# Sch1r2.net
KiCad netlist of a schematic drawn in EAGLE
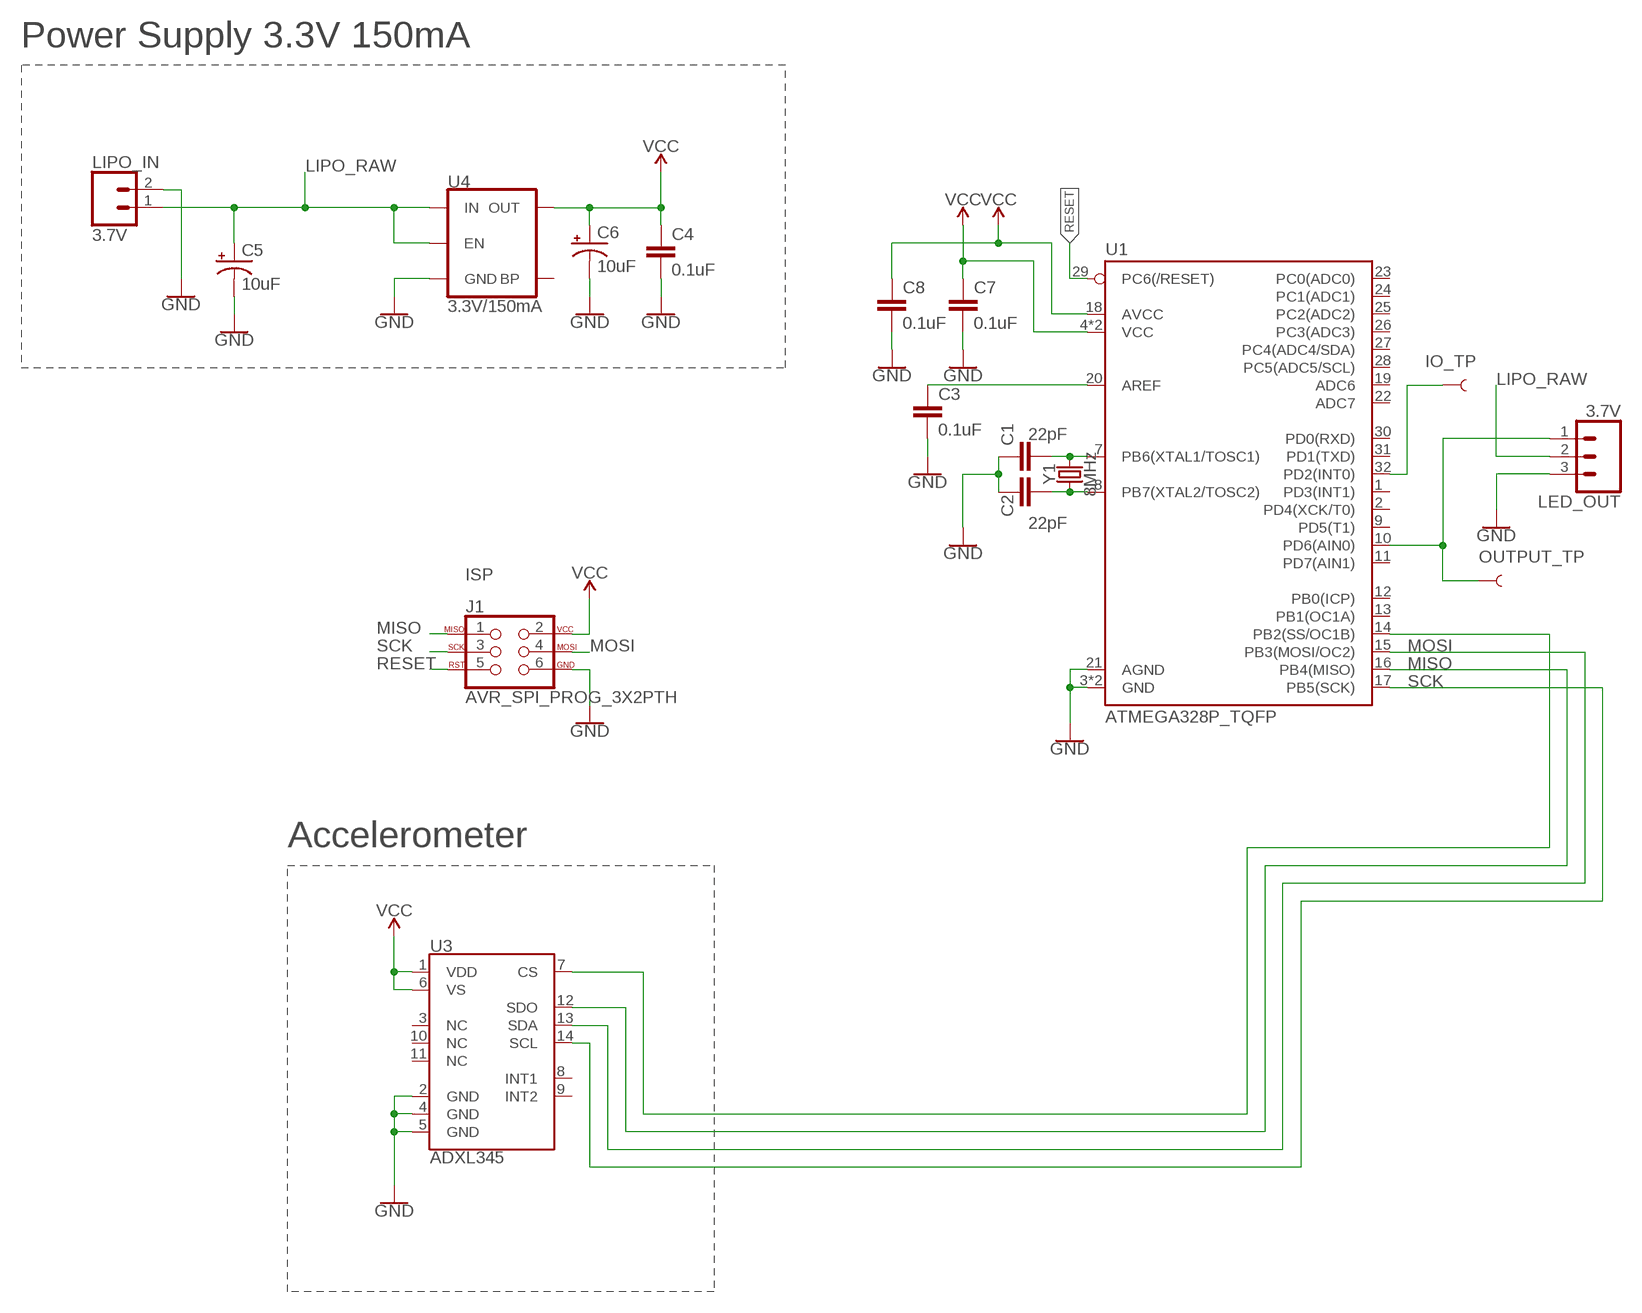
[diagram p0: schematic, sheet 1]

(export (version "E")
  (design (tool "Eeschema 10.0.6"))
  (components
    (comp (ref "C1")
      (value "22pF")
      (footprint "eagle-import:0603")
      (libsource (lib "eagle-import") (part "22PF-0603-50V-5%"))
    )
    (comp (ref "C2")
      (value "22pF")
      (footprint "eagle-import:0603")
      (libsource (lib "eagle-import") (part "22PF-0603-50V-5%"))
    )
    (comp (ref "C3")
      (value "0.1uF")
      (footprint "eagle-import:0402")
      (libsource (lib "eagle-import") (part "0.1UF-0402-16V-10%"))
    )
    (comp (ref "C4")
      (value "0.1uF")
      (footprint "eagle-import:0603")
      (libsource (lib "eagle-import") (part "0.1UF-0603-25V-(+80/-20%)"))
    )
    (comp (ref "C5")
      (value "10uF")
      (footprint "eagle-import:0603-POLAR")
      (libsource (lib "eagle-import") (part "10UF-POLAR-0603-6.3V-20%(TANT)"))
    )
    (comp (ref "C6")
      (value "10uF")
      (footprint "eagle-import:0603-POLAR")
      (libsource (lib "eagle-import") (part "10UF-POLAR-0603-6.3V-20%(TANT)"))
    )
    (comp (ref "C7")
      (value "0.1uF")
      (footprint "eagle-import:0402")
      (libsource (lib "eagle-import") (part "0.1UF-0402-16V-10%"))
    )
    (comp (ref "C8")
      (value "0.1uF")
      (footprint "eagle-import:0402")
      (libsource (lib "eagle-import") (part "0.1UF-0402-16V-10%"))
    )
    (comp (ref "IO_TP")
      (value "TEST-POINT3")
      (footprint "eagle-import:PAD.03X.03")
      (libsource (lib "eagle-import") (part "TEST-POINT3"))
    )
    (comp (ref "J1")
      (value "AVR_SPI_PROG_3X2PTH")
      (footprint "eagle-import:2X3")
      (libsource (lib "eagle-import") (part "AVR_SPI_PROG_3X2PTH"))
    )
    (comp (ref "LED_OUT")
      (value "3.7V")
      (footprint "eagle-import:1X03_LOCK_LONGPADS")
      (libsource (lib "eagle-import") (part "CONN_03LOCK_LONGPADS"))
    )
    (comp (ref "LIPO_IN")
      (value "3.7V")
      (footprint "eagle-import:1X02_LONGPADS")
      (libsource (lib "eagle-import") (part "CONN_02PTH3"))
    )
    (comp (ref "OUTPUT_TP")
      (value "TEST-POINT3")
      (footprint "eagle-import:PAD.03X.03")
      (libsource (lib "eagle-import") (part "TEST-POINT3"))
    )
    (comp (ref "U1")
      (value "ATMEGA328P_TQFP")
      (footprint "eagle-import:TQFP32-08")
      (libsource (lib "eagle-import") (part "ATMEGA328P_TQFP"))
    )
    (comp (ref "U3")
      (value "ADXL345")
      (footprint "eagle-import:LGA-14")
      (libsource (lib "eagle-import") (part "ADXL345"))
    )
    (comp (ref "U4")
      (value "3.3V/150mA")
      (footprint "eagle-import:SOT23-5")
      (libsource (lib "eagle-import") (part "V_REG_MIC52053.3V"))
    )
    (comp (ref "Y1")
      (value "8MHz")
      (footprint "eagle-import:CRYSTAL-SMD-5X3.2-4PAD")
      (libsource (lib "eagle-import") (part "CRYSTAL-8MHZSMD-5X3.2"))
    )
  )
  (nets
    (net (code "1") (name "/LIPO_RAW") (class "Default")
      (node (ref "C5") (pin "+") (pinfunction "+_+") (pintype "passive"))
      (node (ref "LED_OUT") (pin "2") (pinfunction "2_2") (pintype "passive"))
      (node (ref "LIPO_IN") (pin "1") (pinfunction "1_1") (pintype "passive"))
      (node (ref "U4") (pin "1") (pinfunction "IN_1") (pintype "input"))
      (node (ref "U4") (pin "3") (pinfunction "EN_3") (pintype "input"))
    )
    (net (code "2") (name "/MISO") (class "Default")
      (node (ref "J1") (pin "1") (pinfunction "1_1") (pintype "passive"))
      (node (ref "U1") (pin "16") (pinfunction "PB4(MISO)_16") (pintype "bidirectional"))
      (node (ref "U3") (pin "12") (pinfunction "SDO_12") (pintype "bidirectional"))
    )
    (net (code "3") (name "/MOSI") (class "Default")
      (node (ref "J1") (pin "4") (pinfunction "4_4") (pintype "passive"))
      (node (ref "U1") (pin "15") (pinfunction "PB3(MOSI/OC2)_15") (pintype "bidirectional"))
      (node (ref "U3") (pin "13") (pinfunction "SDA_13") (pintype "bidirectional"))
    )
    (net (code "4") (name "/SCK") (class "Default")
      (node (ref "J1") (pin "3") (pinfunction "3_3") (pintype "passive"))
      (node (ref "U1") (pin "17") (pinfunction "PB5(SCK)_17") (pintype "bidirectional"))
      (node (ref "U3") (pin "14") (pinfunction "SCL_14") (pintype "bidirectional"))
    )
    (net (code "5") (name "GND") (class "Default")
      (node (ref "C1") (pin "1") (pinfunction "1_1") (pintype "passive"))
      (node (ref "C2") (pin "1") (pinfunction "1_1") (pintype "passive"))
      (node (ref "C3") (pin "2") (pinfunction "2_2") (pintype "passive"))
      (node (ref "C4") (pin "2") (pinfunction "2_2") (pintype "passive"))
      (node (ref "C5") (pin "-") (pinfunction "-_-") (pintype "passive"))
      (node (ref "C6") (pin "-") (pinfunction "-_-") (pintype "passive"))
      (node (ref "C7") (pin "2") (pinfunction "2_2") (pintype "passive"))
      (node (ref "C8") (pin "2") (pinfunction "2_2") (pintype "passive"))
      (node (ref "J1") (pin "6") (pinfunction "6_6") (pintype "passive"))
      (node (ref "LED_OUT") (pin "3") (pinfunction "3_3") (pintype "passive"))
      (node (ref "LIPO_IN") (pin "2") (pinfunction "2_2") (pintype "passive"))
      (node (ref "U1") (pin "21") (pinfunction "AGND_21") (pintype "bidirectional"))
      (node (ref "U1") (pin "3") (pinfunction "GND_3") (pintype "bidirectional"))
      (node (ref "U1") (pin "5") (pinfunction "GND_5") (pintype "bidirectional"))
      (node (ref "U3") (pin "2") (pinfunction "GND_2") (pintype "bidirectional"))
      (node (ref "U3") (pin "4") (pinfunction "GND_4") (pintype "bidirectional"))
      (node (ref "U3") (pin "5") (pinfunction "GND_5") (pintype "bidirectional"))
      (node (ref "U4") (pin "2") (pinfunction "GND_2") (pintype "input"))
    )
    (net (code "6") (name "Net-(IO_TP-1)") (class "Default")
      (node (ref "IO_TP") (pin "P$1") (pinfunction "1_P$1") (pintype "bidirectional"))
      (node (ref "U1") (pin "32") (pinfunction "PD2(INT0)_32") (pintype "bidirectional"))
    )
    (net (code "7") (name "Net-(OUTPUT_TP-1)") (class "Default")
      (node (ref "LED_OUT") (pin "1") (pinfunction "1_1") (pintype "passive"))
      (node (ref "OUTPUT_TP") (pin "P$1") (pinfunction "1_P$1") (pintype "bidirectional"))
      (node (ref "U1") (pin "10") (pinfunction "PD6(AIN0)_10") (pintype "bidirectional"))
    )
    (net (code "8") (name "Net-(U1-AREF)") (class "Default")
      (node (ref "C3") (pin "1") (pinfunction "1_1") (pintype "passive"))
      (node (ref "U1") (pin "20") (pinfunction "AREF_20") (pintype "bidirectional"))
    )
    (net (code "9") (name "Net-(U1-PB2(SS{slash}OC1B))") (class "Default")
      (node (ref "U1") (pin "14") (pinfunction "PB2(SS/OC1B)_14") (pintype "bidirectional"))
      (node (ref "U3") (pin "7") (pinfunction "CS_7") (pintype "bidirectional"))
    )
    (net (code "10") (name "Net-(U1-PB6(XTAL1{slash}TOSC1))") (class "Default")
      (node (ref "C1") (pin "2") (pinfunction "2_2") (pintype "passive"))
      (node (ref "U1") (pin "7") (pinfunction "PB6(XTAL1/TOSC1)_7") (pintype "bidirectional"))
      (node (ref "Y1") (pin "3") (pinfunction "2_3") (pintype "passive"))
    )
    (net (code "11") (name "Net-(U1-PB7(XTAL2{slash}TOSC2))") (class "Default")
      (node (ref "C2") (pin "2") (pinfunction "2_2") (pintype "passive"))
      (node (ref "U1") (pin "8") (pinfunction "PB7(XTAL2/TOSC2)_8") (pintype "bidirectional"))
      (node (ref "Y1") (pin "1") (pinfunction "1_1") (pintype "passive"))
    )
    (net (code "12") (name "RESET") (class "Default")
      (node (ref "J1") (pin "5") (pinfunction "5_5") (pintype "passive"))
      (node (ref "U1") (pin "29") (pinfunction "PC6(/RESET)_29") (pintype "bidirectional"))
    )
    (net (code "13") (name "VCC") (class "Default")
      (node (ref "C4") (pin "1") (pinfunction "1_1") (pintype "passive"))
      (node (ref "C6") (pin "+") (pinfunction "+_+") (pintype "passive"))
      (node (ref "C7") (pin "1") (pinfunction "1_1") (pintype "passive"))
      (node (ref "C8") (pin "1") (pinfunction "1_1") (pintype "passive"))
      (node (ref "J1") (pin "2") (pinfunction "2_2") (pintype "passive"))
      (node (ref "U1") (pin "18") (pinfunction "AVCC_18") (pintype "bidirectional"))
      (node (ref "U1") (pin "4") (pinfunction "VCC_4") (pintype "bidirectional"))
      (node (ref "U1") (pin "6") (pinfunction "VCC_6") (pintype "bidirectional"))
      (node (ref "U3") (pin "1") (pinfunction "VDD_1") (pintype "bidirectional"))
      (node (ref "U3") (pin "6") (pinfunction "VS_6") (pintype "bidirectional"))
      (node (ref "U4") (pin "5") (pinfunction "OUT_5") (pintype "passive"))
    )
    (net (code "14") (name "unconnected-(U1-ADC6-Pad19)") (class "Default")
      (node (ref "U1") (pin "19") (pinfunction "ADC6_19") (pintype "bidirectional"))
    )
    (net (code "15") (name "unconnected-(U1-ADC7-Pad22)") (class "Default")
      (node (ref "U1") (pin "22") (pinfunction "ADC7_22") (pintype "bidirectional"))
    )
    (net (code "16") (name "unconnected-(U1-PB0(ICP)-Pad12)") (class "Default")
      (node (ref "U1") (pin "12") (pinfunction "PB0(ICP)_12") (pintype "bidirectional"))
    )
    (net (code "17") (name "unconnected-(U1-PB1(OC1A)-Pad13)") (class "Default")
      (node (ref "U1") (pin "13") (pinfunction "PB1(OC1A)_13") (pintype "bidirectional"))
    )
    (net (code "18") (name "unconnected-(U1-PC0(ADC0)-Pad23)") (class "Default")
      (node (ref "U1") (pin "23") (pinfunction "PC0(ADC0)_23") (pintype "bidirectional"))
    )
    (net (code "19") (name "unconnected-(U1-PC1(ADC1)-Pad24)") (class "Default")
      (node (ref "U1") (pin "24") (pinfunction "PC1(ADC1)_24") (pintype "bidirectional"))
    )
    (net (code "20") (name "unconnected-(U1-PC2(ADC2)-Pad25)") (class "Default")
      (node (ref "U1") (pin "25") (pinfunction "PC2(ADC2)_25") (pintype "bidirectional"))
    )
    (net (code "21") (name "unconnected-(U1-PC3(ADC3)-Pad26)") (class "Default")
      (node (ref "U1") (pin "26") (pinfunction "PC3(ADC3)_26") (pintype "bidirectional"))
    )
    (net (code "22") (name "unconnected-(U1-PC4(ADC4{slash}SDA)-Pad27)") (class "Default")
      (node (ref "U1") (pin "27") (pinfunction "PC4(ADC4/SDA)_27") (pintype "bidirectional"))
    )
    (net (code "23") (name "unconnected-(U1-PC5(ADC5{slash}SCL)-Pad28)") (class "Default")
      (node (ref "U1") (pin "28") (pinfunction "PC5(ADC5/SCL)_28") (pintype "bidirectional"))
    )
    (net (code "24") (name "unconnected-(U1-PD0(RXD)-Pad30)") (class "Default")
      (node (ref "U1") (pin "30") (pinfunction "PD0(RXD)_30") (pintype "bidirectional"))
    )
    (net (code "25") (name "unconnected-(U1-PD1(TXD)-Pad31)") (class "Default")
      (node (ref "U1") (pin "31") (pinfunction "PD1(TXD)_31") (pintype "bidirectional"))
    )
    (net (code "26") (name "unconnected-(U1-PD3(INT1)-Pad1)") (class "Default")
      (node (ref "U1") (pin "1") (pinfunction "PD3(INT1)_1") (pintype "bidirectional"))
    )
    (net (code "27") (name "unconnected-(U1-PD4(XCK{slash}T0)-Pad2)") (class "Default")
      (node (ref "U1") (pin "2") (pinfunction "PD4(XCK/T0)_2") (pintype "bidirectional"))
    )
    (net (code "28") (name "unconnected-(U1-PD5(T1)-Pad9)") (class "Default")
      (node (ref "U1") (pin "9") (pinfunction "PD5(T1)_9") (pintype "bidirectional"))
    )
    (net (code "29") (name "unconnected-(U1-PD7(AIN1)-Pad11)") (class "Default")
      (node (ref "U1") (pin "11") (pinfunction "PD7(AIN1)_11") (pintype "bidirectional"))
    )
    (net (code "30") (name "unconnected-(U3-INT1-Pad8)") (class "Default")
      (node (ref "U3") (pin "8") (pinfunction "INT1_8") (pintype "bidirectional"))
    )
    (net (code "31") (name "unconnected-(U3-INT2-Pad9)") (class "Default")
      (node (ref "U3") (pin "9") (pinfunction "INT2_9") (pintype "bidirectional"))
    )
    (net (code "32") (name "unconnected-(U3-NC-Pad3)") (class "Default")
      (node (ref "U3") (pin "3") (pinfunction "NC_3") (pintype "bidirectional"))
    )
    (net (code "33") (name "unconnected-(U3-NC-Pad10)") (class "Default")
      (node (ref "U3") (pin "10") (pinfunction "NC_10") (pintype "bidirectional"))
    )
    (net (code "34") (name "unconnected-(U3-NC-Pad11)") (class "Default")
      (node (ref "U3") (pin "11") (pinfunction "NC_11") (pintype "bidirectional"))
    )
    (net (code "35") (name "unconnected-(U4-BP-Pad4)") (class "Default")
      (node (ref "U4") (pin "4") (pinfunction "BP_4") (pintype "input"))
    )
  )
)
